# ohmHandle4seg_V123D_noISPV2.net
KiCad netlist of a schematic drawn in EAGLE
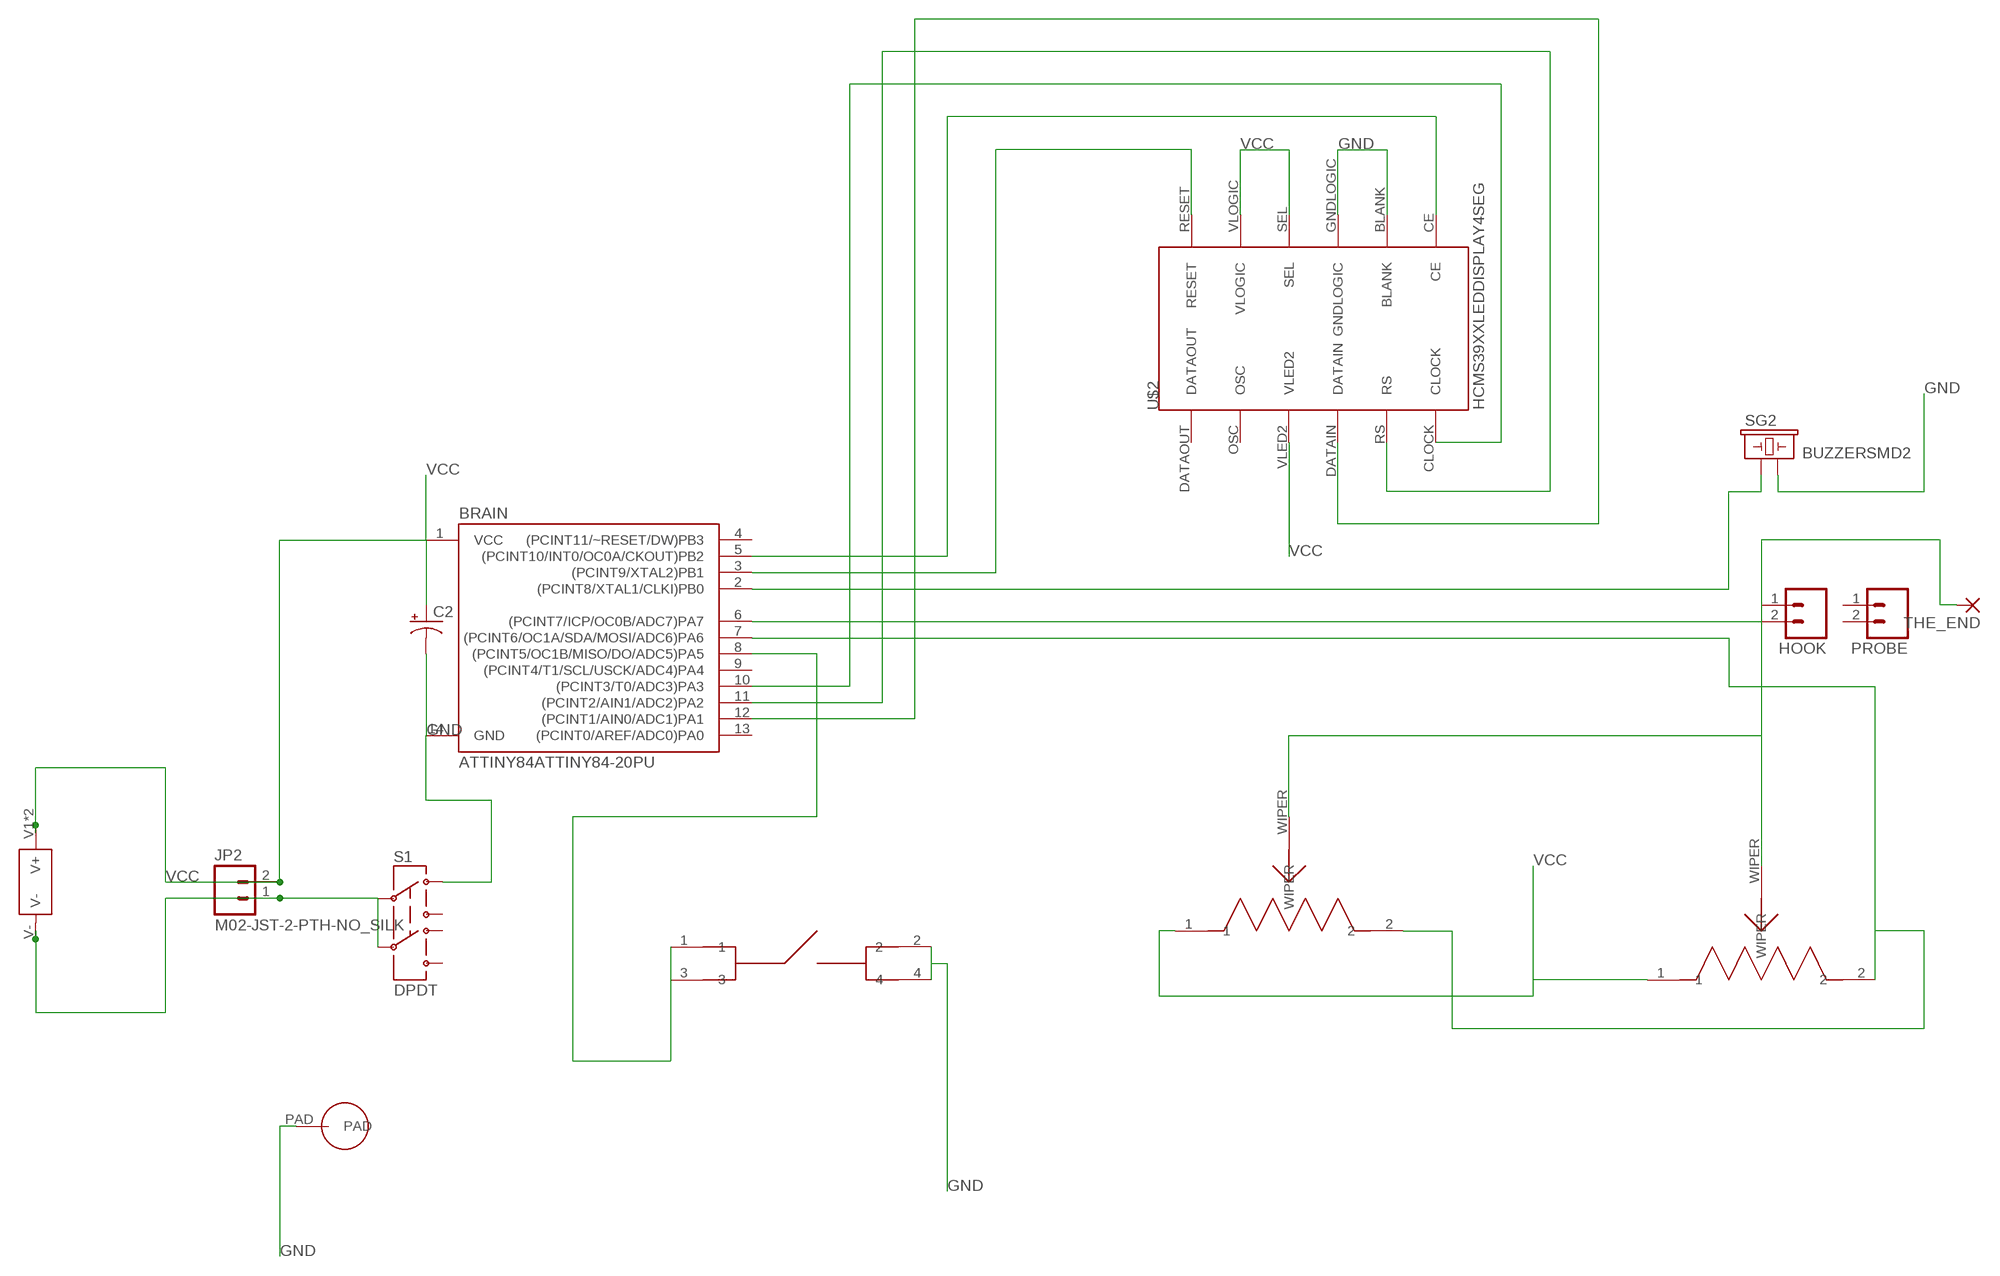
[diagram p0: schematic, sheet 1]

(export (version "E")
  (design (tool "Eeschema 10.0.6"))
  (components
    (comp (ref "BRAIN")
      (value "ATTINY84ATTINY84-20PU")
      (footprint "eagle-import:DIL14")
      (libsource (lib "eagle-import") (part "ATTINY84ATTINY84-20PU"))
    )
    (comp (ref "C2")
      (value "CAP_POLPTH2")
      (footprint "eagle-import:CPOL-RADIAL-10UF-25V")
      (libsource (lib "eagle-import") (part "CAP_POLPTH2"))
    )
    (comp (ref "HOOK")
      (value "M02LOCK_LONGPADS")
      (footprint "eagle-import:1X02_LOCK_LONGPADS")
      (libsource (lib "eagle-import") (part "M02LOCK_LONGPADS"))
    )
    (comp (ref "J1")
      (value "HOLDER-BAT-D20.32")
      (footprint "eagle-import:2032-SMD-D20.32")
      (libsource (lib "eagle-import") (part "HOLDER-BAT-D20.32"))
    )
    (comp (ref "JP2")
      (value "M02-JST-2-PTH-NO_SILK")
      (footprint "eagle-import:JST-2-PTH-NS")
      (libsource (lib "eagle-import") (part "M02-JST-2-PTH-NO_SILK"))
    )
    (comp (ref "PROBE")
      (value "M02LOCK_LONGPADS")
      (footprint "eagle-import:1X02_LOCK_LONGPADS")
      (libsource (lib "eagle-import") (part "M02LOCK_LONGPADS"))
    )
    (comp (ref "S1")
      (value "DPDT")
      (footprint "eagle-import:AYZ0202")
      (libsource (lib "eagle-import") (part "SWITCH-DPDTAYZ0202"))
    )
    (comp (ref "SG2")
      (value "BUZZERSMD2")
      (footprint "eagle-import:BUZZER-CCV")
      (libsource (lib "eagle-import") (part "BUZZERSMD2"))
    )
    (comp (ref "THE_END")
      (value "SMD5")
      (footprint "eagle-import:SMD2,54-5,08")
      (libsource (lib "eagle-import") (part "SMD5"))
    )
    (comp (ref "U$2")
      (value "HCMS39XXLEDDISPLAY4SEG")
      (footprint "eagle-import:LEDDISPLAY4SEG")
      (libsource (lib "eagle-import") (part "HCMS39XXLEDDISPLAY4SEG"))
    )
    (comp (ref "U$3")
      (value "THUMBPOT10MM")
      (footprint "eagle-import:THUMBPOT10MM")
      (libsource (lib "eagle-import") (part "THUMBPOT10MM"))
    )
    (comp (ref "U$6")
      (value "LARGEPAD")
      (footprint "eagle-import:LARGEPAD")
      (libsource (lib "eagle-import") (part "LARGEPAD"))
    )
    (comp (ref "U$7")
      (value "THUMBPOT3352")
      (footprint "eagle-import:THUMBPOT3352P")
      (libsource (lib "eagle-import") (part "THUMBPOT3352"))
    )
    (comp (ref "U$9")
      (value "BUTTONSMD")
      (footprint "eagle-import:TACTILESWITCHSMD")
      (libsource (lib "eagle-import") (part "BUTTONSMD"))
    )
  )
  (nets
    (net (code "1") (name "/GND") (class "Default")
      (node (ref "BRAIN") (pin "14") (pinfunction "GND_14") (pintype "bidirectional"))
      (node (ref "C2") (pin "2") (pinfunction "-_2") (pintype "passive"))
      (node (ref "S1") (pin "1") (pinfunction "1_1") (pintype "bidirectional"))
      (node (ref "SG2") (pin "-") (pinfunction "2_-") (pintype "passive"))
      (node (ref "U$2") (pin "BLANK") (pinfunction "BLANK_BLANK") (pintype "bidirectional"))
      (node (ref "U$2") (pin "GNDLOGIC") (pinfunction "GNDLOGIC_GNDLOGIC") (pintype "bidirectional"))
      (node (ref "U$6") (pin "PAD") (pinfunction "PAD_PAD") (pintype "bidirectional"))
      (node (ref "U$9") (pin "2") (pinfunction "2_2") (pintype "bidirectional"))
      (node (ref "U$9") (pin "4") (pinfunction "4_4") (pintype "bidirectional"))
    )
    (net (code "2") (name "/VCC") (class "Default")
      (node (ref "BRAIN") (pin "1") (pinfunction "VCC_1") (pintype "bidirectional"))
      (node (ref "C2") (pin "1") (pinfunction "+_1") (pintype "passive"))
      (node (ref "J1") (pin "V1") (pinfunction "V+_V1") (pintype "bidirectional"))
      (node (ref "J1") (pin "V2") (pinfunction "V+_V2") (pintype "bidirectional"))
      (node (ref "JP2") (pin "2") (pinfunction "2_2") (pintype "passive"))
      (node (ref "U$2") (pin "SEL") (pinfunction "SEL_SEL") (pintype "bidirectional"))
      (node (ref "U$2") (pin "VLED2") (pinfunction "VLED2_VLED2") (pintype "bidirectional"))
      (node (ref "U$2") (pin "VLOGIC") (pinfunction "VLOGIC_VLOGIC") (pintype "bidirectional"))
      (node (ref "U$3") (pin "1") (pinfunction "1_1") (pintype "bidirectional"))
      (node (ref "U$7") (pin "1") (pinfunction "1_1") (pintype "bidirectional"))
    )
    (net (code "3") (name "Net-(BRAIN-(PCINT1{slash}AIN0{slash}ADC1)PA1)") (class "Default")
      (node (ref "BRAIN") (pin "12") (pinfunction "(PCINT1/AIN0/ADC1)PA1_12") (pintype "bidirectional"))
      (node (ref "U$2") (pin "DATAIN") (pinfunction "DATAIN_DATAIN") (pintype "bidirectional"))
    )
    (net (code "4") (name "Net-(BRAIN-(PCINT2{slash}AIN1{slash}ADC2)PA2)") (class "Default")
      (node (ref "BRAIN") (pin "11") (pinfunction "(PCINT2/AIN1/ADC2)PA2_11") (pintype "bidirectional"))
      (node (ref "U$2") (pin "RS") (pinfunction "RS_RS") (pintype "bidirectional"))
    )
    (net (code "5") (name "Net-(BRAIN-(PCINT3{slash}T0{slash}ADC3)PA3)") (class "Default")
      (node (ref "BRAIN") (pin "10") (pinfunction "(PCINT3/T0/ADC3)PA3_10") (pintype "bidirectional"))
      (node (ref "U$2") (pin "CLOCK") (pinfunction "CLOCK_CLOCK") (pintype "bidirectional"))
    )
    (net (code "6") (name "Net-(BRAIN-(PCINT5{slash}OC1B{slash}MISO{slash}DO{slash}ADC5)PA5)") (class "Default")
      (node (ref "BRAIN") (pin "8") (pinfunction "(PCINT5/OC1B/MISO/DO/ADC5)PA5_8") (pintype "bidirectional"))
      (node (ref "U$9") (pin "1") (pinfunction "1_1") (pintype "bidirectional"))
      (node (ref "U$9") (pin "3") (pinfunction "3_3") (pintype "bidirectional"))
    )
    (net (code "7") (name "Net-(BRAIN-(PCINT6{slash}OC1A{slash}SDA{slash}MOSI{slash}ADC6)PA6)") (class "Default")
      (node (ref "BRAIN") (pin "7") (pinfunction "(PCINT6/OC1A/SDA/MOSI/ADC6)PA6_7") (pintype "bidirectional"))
      (node (ref "U$3") (pin "2") (pinfunction "2_2") (pintype "bidirectional"))
      (node (ref "U$7") (pin "2") (pinfunction "2_2") (pintype "bidirectional"))
    )
    (net (code "8") (name "Net-(BRAIN-(PCINT7{slash}ICP{slash}OC0B{slash}ADC7)PA7)") (class "Default")
      (node (ref "BRAIN") (pin "6") (pinfunction "(PCINT7/ICP/OC0B/ADC7)PA7_6") (pintype "bidirectional"))
      (node (ref "HOOK") (pin "1") (pinfunction "1_1") (pintype "passive"))
      (node (ref "HOOK") (pin "2") (pinfunction "2_2") (pintype "passive"))
      (node (ref "THE_END") (pin "1") (pinfunction "P_1") (pintype "passive"))
      (node (ref "U$3") (pin "WIPER") (pinfunction "WIPER_WIPER") (pintype "bidirectional"))
      (node (ref "U$7") (pin "WIPER") (pinfunction "WIPER_WIPER") (pintype "bidirectional"))
    )
    (net (code "9") (name "Net-(BRAIN-(PCINT8{slash}XTAL1{slash}CLKI)PB0)") (class "Default")
      (node (ref "BRAIN") (pin "2") (pinfunction "(PCINT8/XTAL1/CLKI)PB0_2") (pintype "bidirectional"))
      (node (ref "SG2") (pin "+") (pinfunction "1_+") (pintype "passive"))
    )
    (net (code "10") (name "Net-(BRAIN-(PCINT9{slash}XTAL2)PB1)") (class "Default")
      (node (ref "BRAIN") (pin "3") (pinfunction "(PCINT9/XTAL2)PB1_3") (pintype "bidirectional"))
      (node (ref "U$2") (pin "RESET") (pinfunction "RESET_RESET") (pintype "bidirectional"))
    )
    (net (code "11") (name "Net-(BRAIN-(PCINT10{slash}INT0{slash}OC0A{slash}CKOUT)PB2)") (class "Default")
      (node (ref "BRAIN") (pin "5") (pinfunction "(PCINT10/INT0/OC0A/CKOUT)PB2_5") (pintype "bidirectional"))
      (node (ref "U$2") (pin "CE") (pinfunction "CE_CE") (pintype "bidirectional"))
    )
    (net (code "12") (name "Net-(J1-PadV-)") (class "Default")
      (node (ref "J1") (pin "V-") (pinfunction "V-_V-") (pintype "bidirectional"))
      (node (ref "JP2") (pin "1") (pinfunction "1_1") (pintype "passive"))
      (node (ref "S1") (pin "2") (pinfunction "2_2") (pintype "bidirectional"))
      (node (ref "S1") (pin "5") (pinfunction "5_5") (pintype "bidirectional"))
    )
    (net (code "13") (name "unconnected-(BRAIN-(PCINT0{slash}AREF{slash}ADC0)PA0-Pad13)") (class "Default")
      (node (ref "BRAIN") (pin "13") (pinfunction "(PCINT0/AREF/ADC0)PA0_13") (pintype "bidirectional"))
    )
    (net (code "14") (name "unconnected-(BRAIN-(PCINT4{slash}T1{slash}SCL{slash}USCK{slash}ADC4)PA4-Pad9)") (class "Default")
      (node (ref "BRAIN") (pin "9") (pinfunction "(PCINT4/T1/SCL/USCK/ADC4)PA4_9") (pintype "bidirectional"))
    )
    (net (code "15") (name "unconnected-(BRAIN-(PCINT11{slash}~{RESET{slash}DW})PB3-Pad4)") (class "Default")
      (node (ref "BRAIN") (pin "4") (pinfunction "(PCINT11/~{RESET/DW})PB3_4") (pintype "bidirectional"))
    )
    (net (code "16") (name "unconnected-(PROBE-Pad1)") (class "Default")
      (node (ref "PROBE") (pin "1") (pinfunction "1_1") (pintype "passive"))
    )
    (net (code "17") (name "unconnected-(PROBE-Pad2)") (class "Default")
      (node (ref "PROBE") (pin "2") (pinfunction "2_2") (pintype "passive"))
    )
    (net (code "18") (name "unconnected-(S1-Pad3)") (class "Default")
      (node (ref "S1") (pin "3") (pinfunction "3_3") (pintype "bidirectional"))
    )
    (net (code "19") (name "unconnected-(S1-Pad4)") (class "Default")
      (node (ref "S1") (pin "4") (pinfunction "4_4") (pintype "bidirectional"))
    )
    (net (code "20") (name "unconnected-(S1-Pad6)") (class "Default")
      (node (ref "S1") (pin "6") (pinfunction "6_6") (pintype "bidirectional"))
    )
    (net (code "21") (name "unconnected-(U$2-PadDATAOUT)") (class "Default")
      (node (ref "U$2") (pin "DATAOUT") (pinfunction "DATAOUT_DATAOUT") (pintype "bidirectional"))
    )
    (net (code "22") (name "unconnected-(U$2-PadOSC)") (class "Default")
      (node (ref "U$2") (pin "OSC") (pinfunction "OSC_OSC") (pintype "bidirectional"))
    )
  )
)
